# transistor_as_amplifier.net
KiCad netlist of a schematic drawn in EAGLE
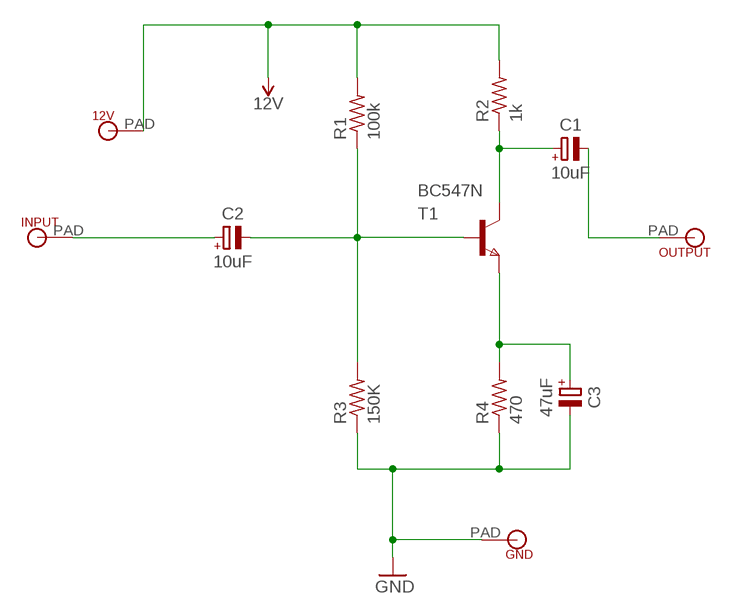
[diagram p0: schematic, sheet 1]

(export (version "E")
  (design (tool "Eeschema 10.0.6"))
  (components
    (comp (ref "12V")
      (value "MICROBIT_PAD")
      (footprint "eagle-import:MICROBIT_PAD")
      (libsource (lib "eagle-import") (part "MICROBIT_PAD"))
    )
    (comp (ref "C1")
      (value "10uF")
      (footprint "eagle-import:C_E2-4")
      (libsource (lib "eagle-import") (part "CAPACITOR_POL-E2-4"))
    )
    (comp (ref "C2")
      (value "10uF")
      (footprint "eagle-import:C_E2-4")
      (libsource (lib "eagle-import") (part "CAPACITOR_POL-E2-4"))
    )
    (comp (ref "C3")
      (value "47uF")
      (footprint "eagle-import:C_E2-4")
      (libsource (lib "eagle-import") (part "CAPACITOR_POL-E2-4"))
    )
    (comp (ref "GND")
      (value "MICROBIT_PAD")
      (footprint "eagle-import:MICROBIT_PAD")
      (libsource (lib "eagle-import") (part "MICROBIT_PAD"))
    )
    (comp (ref "INPUT")
      (value "MICROBIT_PAD")
      (footprint "eagle-import:MICROBIT_PAD")
      (libsource (lib "eagle-import") (part "MICROBIT_PAD"))
    )
    (comp (ref "OUTPUT")
      (value "MICROBIT_PAD")
      (footprint "eagle-import:MICROBIT_PAD")
      (libsource (lib "eagle-import") (part "MICROBIT_PAD"))
    )
    (comp (ref "R1")
      (value "100k")
      (footprint "eagle-import:0207_12")
      (libsource (lib "eagle-import") (part "R-US_0207/12"))
    )
    (comp (ref "R2")
      (value "1k")
      (footprint "eagle-import:0207_12")
      (libsource (lib "eagle-import") (part "R-US_0207/12"))
    )
    (comp (ref "R3")
      (value "150K")
      (footprint "eagle-import:0207_12")
      (libsource (lib "eagle-import") (part "R-US_0207/12"))
    )
    (comp (ref "R4")
      (value "470")
      (footprint "eagle-import:0207_12")
      (libsource (lib "eagle-import") (part "R-US_0207/12"))
    )
    (comp (ref "T1")
      (value "BC547N")
      (footprint "eagle-import:TO92")
      (fields (field (name "MF") "ON Semiconductor") (field (name "MP") "BC547"))
      (libsource (lib "eagle-import") (part "BC547N"))
    )
  )
  (nets
    (net (code "1") (name "12V") (class "Default")
      (node (ref "12V") (pin "PAD") (pinfunction "P$1_PAD") (pintype "bidirectional"))
      (node (ref "R1") (pin "2") (pinfunction "2_2") (pintype "passive"))
      (node (ref "R2") (pin "2") (pinfunction "2_2") (pintype "passive"))
    )
    (net (code "2") (name "GND") (class "Default")
      (node (ref "C3") (pin "-") (pinfunction "-_-") (pintype "passive"))
      (node (ref "GND") (pin "PAD") (pinfunction "P$1_PAD") (pintype "bidirectional"))
      (node (ref "R3") (pin "1") (pinfunction "1_1") (pintype "passive"))
      (node (ref "R4") (pin "1") (pinfunction "1_1") (pintype "passive"))
    )
    (net (code "3") (name "Net-(INPUT-P$1)") (class "Default")
      (node (ref "C2") (pin "+") (pinfunction "+_+") (pintype "passive"))
      (node (ref "INPUT") (pin "PAD") (pinfunction "P$1_PAD") (pintype "bidirectional"))
    )
    (net (code "4") (name "Net-(OUTPUT-P$1)") (class "Default")
      (node (ref "C1") (pin "-") (pinfunction "-_-") (pintype "passive"))
      (node (ref "OUTPUT") (pin "PAD") (pinfunction "P$1_PAD") (pintype "bidirectional"))
    )
    (net (code "5") (name "Net-(T1-B)") (class "Default")
      (node (ref "C2") (pin "-") (pinfunction "-_-") (pintype "passive"))
      (node (ref "R1") (pin "1") (pinfunction "1_1") (pintype "passive"))
      (node (ref "R3") (pin "2") (pinfunction "2_2") (pintype "passive"))
      (node (ref "T1") (pin "2") (pinfunction "B_2") (pintype "passive"))
    )
    (net (code "6") (name "Net-(T1-C)") (class "Default")
      (node (ref "C1") (pin "+") (pinfunction "+_+") (pintype "passive"))
      (node (ref "R2") (pin "1") (pinfunction "1_1") (pintype "passive"))
      (node (ref "T1") (pin "1") (pinfunction "C_1") (pintype "passive"))
    )
    (net (code "7") (name "Net-(T1-E)") (class "Default")
      (node (ref "C3") (pin "+") (pinfunction "+_+") (pintype "passive"))
      (node (ref "R4") (pin "2") (pinfunction "2_2") (pintype "passive"))
      (node (ref "T1") (pin "3") (pinfunction "E_3") (pintype "passive"))
    )
  )
)
